# avr-isp-so8-adapter.net
KiCad netlist of a schematic drawn in EAGLE
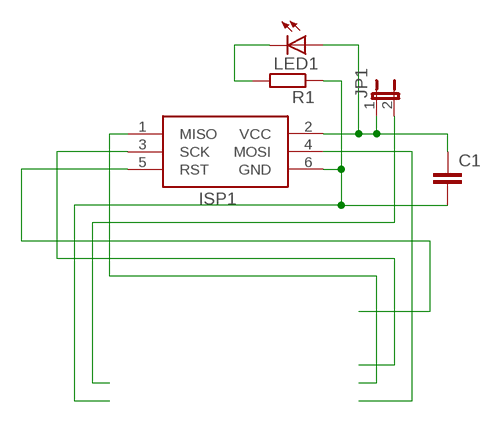
[diagram p0: schematic, sheet 1]

(export (version "E")
  (design (tool "Eeschema 10.0.6"))
  (components
    (comp (ref "C1")
      (value "C-EUC0805K")
      (footprint "eagle-import:C0805K")
      (libsource (lib "eagle-import") (part "C-EUC0805K"))
    )
    (comp (ref "ISP1")
      (value "AVRISP-6")
      (footprint "eagle-import:AVRISP")
      (libsource (lib "eagle-import") (part "AVRISP-6"))
    )
    (comp (ref "JP1")
      (value "JUMPER-2SMD-NO")
      (footprint "eagle-import:SJ_2S-NO")
      (libsource (lib "eagle-import") (part "JUMPER-2SMD-NO"))
    )
    (comp (ref "LED1")
      (value "LEDCHIPLED_0805")
      (footprint "eagle-import:CHIPLED_0805")
      (libsource (lib "eagle-import") (part "LEDCHIPLED_0805"))
    )
    (comp (ref "R1")
      (value "R-EU_R0805")
      (footprint "eagle-import:R0805")
      (libsource (lib "eagle-import") (part "R-EU_R0805"))
    )
  )
  (nets
    (net (code "1") (name "Net-(ISP1-GND)") (class "Default")
      (node (ref "C1") (pin "2") (pinfunction "2_2") (pintype "passive"))
      (node (ref "ISP1") (pin "6") (pinfunction "GND_6") (pintype "power_in"))
      (node (ref "R1") (pin "1") (pinfunction "1_1") (pintype "passive"))
    )
    (net (code "2") (name "Net-(ISP1-VCC)") (class "Default")
      (node (ref "C1") (pin "1") (pinfunction "1_1") (pintype "passive"))
      (node (ref "ISP1") (pin "2") (pinfunction "VCC_2") (pintype "power_in"))
      (node (ref "JP1") (pin "1") (pinfunction "1_1") (pintype "passive"))
      (node (ref "LED1") (pin "A") (pinfunction "A_A") (pintype "passive"))
    )
    (net (code "3") (name "Net-(LED1-PadC)") (class "Default")
      (node (ref "LED1") (pin "C") (pinfunction "C_C") (pintype "passive"))
      (node (ref "R1") (pin "2") (pinfunction "2_2") (pintype "passive"))
    )
    (net (code "4") (name "unconnected-(ISP1-MISO-Pad1)") (class "Default")
      (node (ref "ISP1") (pin "1") (pinfunction "MISO_1") (pintype "input"))
    )
    (net (code "5") (name "unconnected-(ISP1-MOSI-Pad4)") (class "Default")
      (node (ref "ISP1") (pin "4") (pinfunction "MOSI_4") (pintype "output"))
    )
    (net (code "6") (name "unconnected-(ISP1-RST-Pad5)") (class "Default")
      (node (ref "ISP1") (pin "5") (pinfunction "RST_5") (pintype "output"))
    )
    (net (code "7") (name "unconnected-(ISP1-SCK-Pad3)") (class "Default")
      (node (ref "ISP1") (pin "3") (pinfunction "SCK_3") (pintype "output"))
    )
    (net (code "8") (name "unconnected-(JP1-Pad2)") (class "Default")
      (node (ref "JP1") (pin "2") (pinfunction "2_2") (pintype "passive"))
    )
  )
)
